# LB_BIT_1OUT-LARGE-v03_1_1x.net
KiCad netlist of a schematic drawn in EAGLE
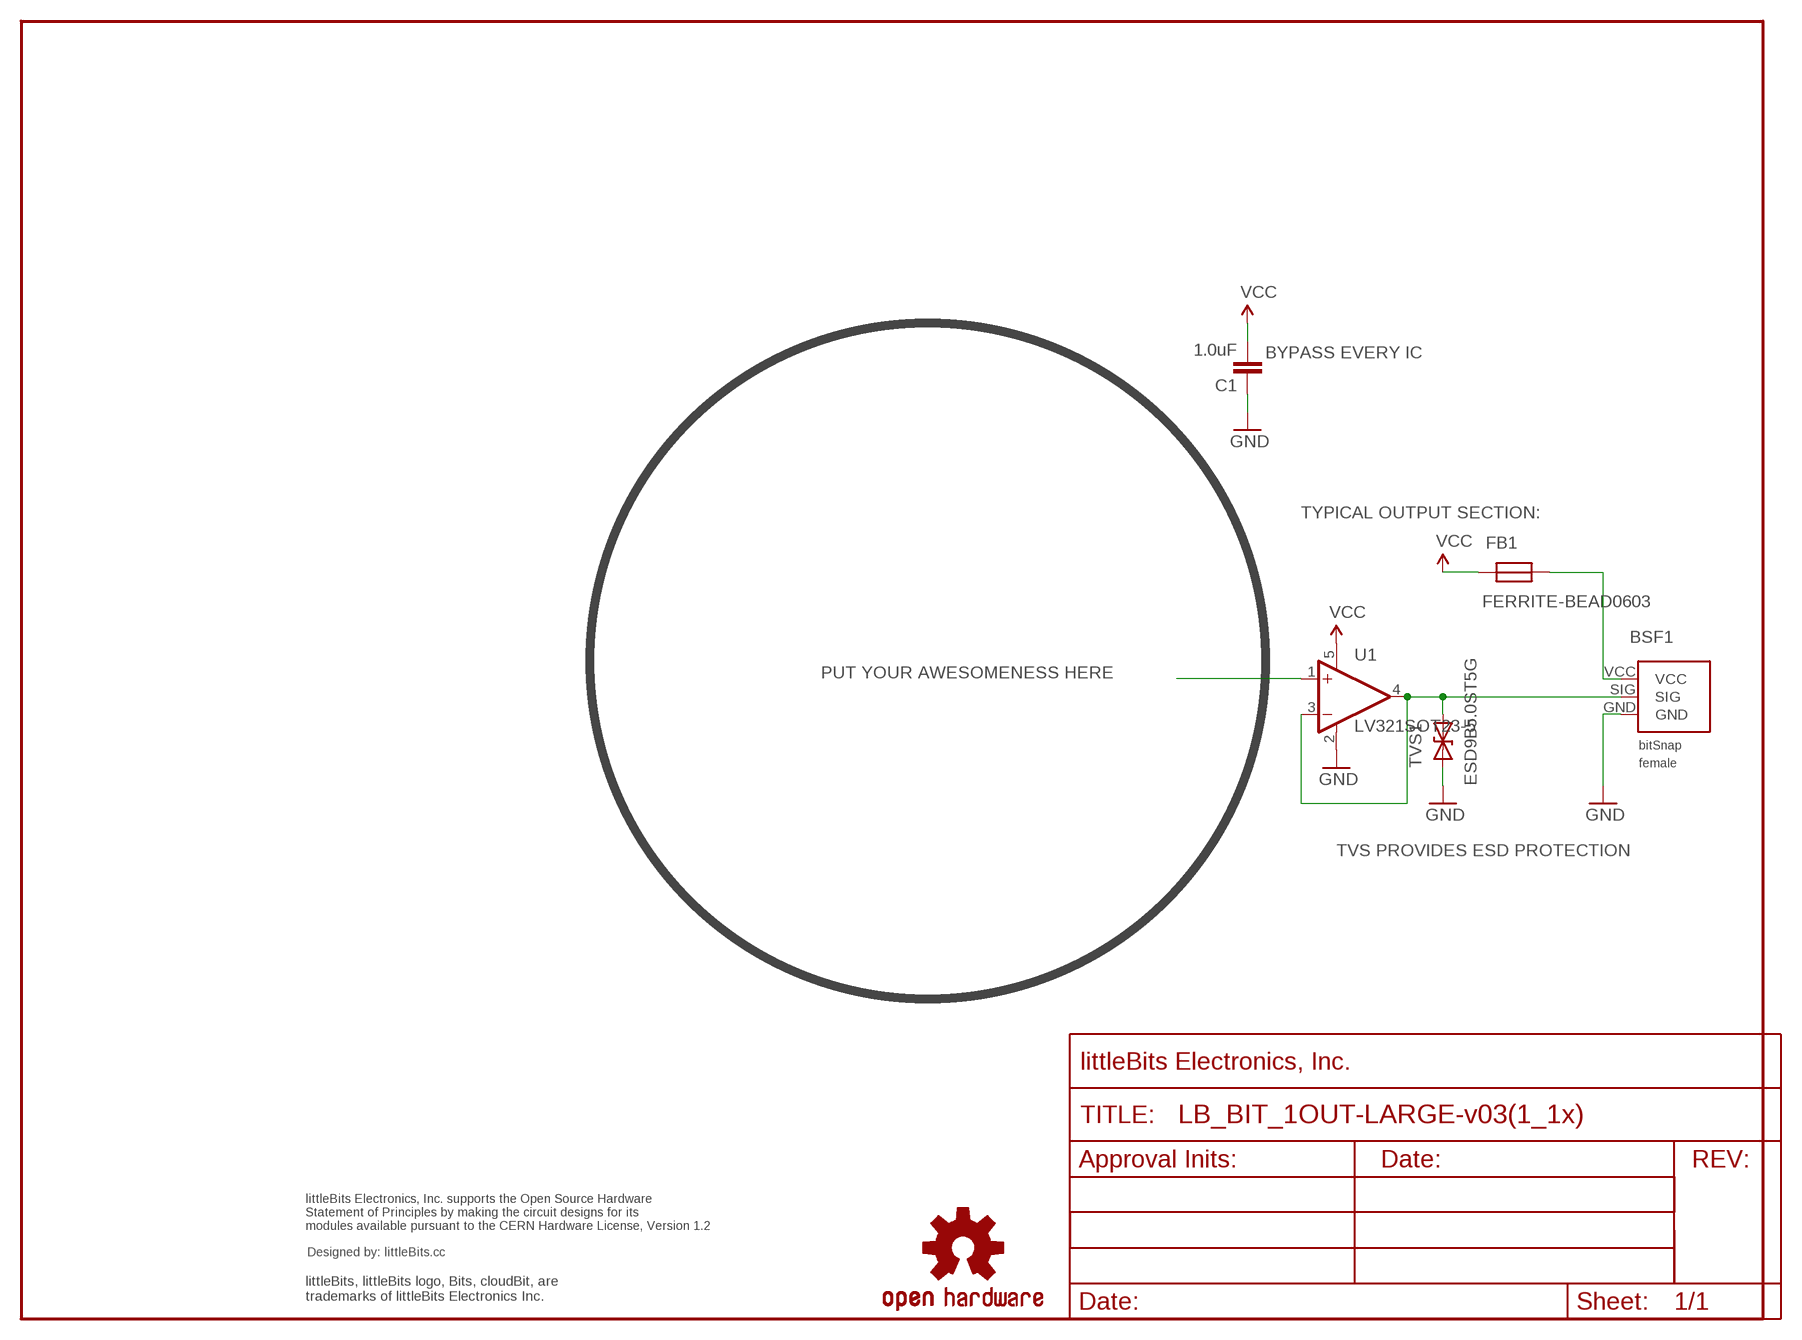
[diagram p0: schematic, sheet 1]

(export (version "E")
  (design (tool "Eeschema 10.0.6"))
  (components
    (comp (ref "BSF1")
      (value "BITSNAP_V03_FEMALE")
      (footprint "eagle-import:BITSNAP_V03_FEMALE")
      (libsource (lib "eagle-import") (part "BITSNAP_V03_FEMALE"))
    )
    (comp (ref "C1")
      (value "1.0uF")
      (footprint "eagle-import:CAP-0603")
      (libsource (lib "eagle-import") (part "CAPCAP-0603"))
    )
    (comp (ref "FB1")
      (value "FERRITE-BEAD0603")
      (footprint "eagle-import:R0603")
      (libsource (lib "eagle-import") (part "FERRITE-BEAD0603"))
    )
    (comp (ref "FRAME1")
      (value "FRAME-LETTERWHITEMASK")
      (footprint "eagle-import:FABDWG01-WHITEMASK")
      (libsource (lib "eagle-import") (part "FRAME-LETTERWHITEMASK"))
    )
    (comp (ref "TVS1")
      (value "ESD9B5.0ST5G")
      (footprint "eagle-import:SOD-923")
      (libsource (lib "eagle-import") (part "DIODE-TVSSOD-923"))
    )
    (comp (ref "U$3")
      (value "OSHW-LOGOL")
      (footprint "eagle-import:OSHW-LOGO-L")
      (libsource (lib "eagle-import") (part "OSHW-LOGOL"))
    )
    (comp (ref "U$4")
      (value "OSHWCREDIT")
      (footprint "eagle-import:OSHWCREDIT")
      (libsource (lib "eagle-import") (part "OSHWCREDIT"))
    )
    (comp (ref "U1")
      (value "LV321SOT23-5")
      (footprint "eagle-import:SOT23-5")
      (libsource (lib "eagle-import") (part "LV321SOT23-5"))
    )
  )
  (nets
    (net (code "1") (name "GND") (class "Default")
      (node (ref "BSF1") (pin "GND") (pinfunction "GND_GND") (pintype "bidirectional"))
      (node (ref "C1") (pin "1") (pinfunction "1_1") (pintype "passive"))
      (node (ref "TVS1") (pin "1") (pinfunction "A_1") (pintype "passive"))
      (node (ref "U1") (pin "2") (pinfunction "V-_2") (pintype "power_in"))
    )
    (net (code "2") (name "Net-(FB1-P$1)") (class "Default")
      (node (ref "BSF1") (pin "VCC") (pinfunction "VCC_VCC") (pintype "bidirectional"))
      (node (ref "FB1") (pin "1") (pinfunction "P$1_1") (pintype "bidirectional"))
    )
    (net (code "3") (name "Net-(TVS1-C)") (class "Default")
      (node (ref "BSF1") (pin "SIG") (pinfunction "SIG_SIG") (pintype "bidirectional"))
      (node (ref "TVS1") (pin "2") (pinfunction "C_2") (pintype "passive"))
      (node (ref "U1") (pin "3") (pinfunction "-IN_3") (pintype "input"))
      (node (ref "U1") (pin "4") (pinfunction "OUT_4") (pintype "output"))
    )
    (net (code "4") (name "VCC") (class "Default")
      (node (ref "C1") (pin "2") (pinfunction "2_2") (pintype "passive"))
      (node (ref "FB1") (pin "2") (pinfunction "P$2_2") (pintype "bidirectional"))
      (node (ref "U1") (pin "5") (pinfunction "V+_5") (pintype "power_in"))
    )
    (net (code "5") (name "unconnected-(U1-+IN-Pad1)") (class "Default")
      (node (ref "U1") (pin "1") (pinfunction "+IN_1") (pintype "input"))
    )
  )
)
